# Switch.net
KiCad netlist of a schematic drawn in Altium Designer
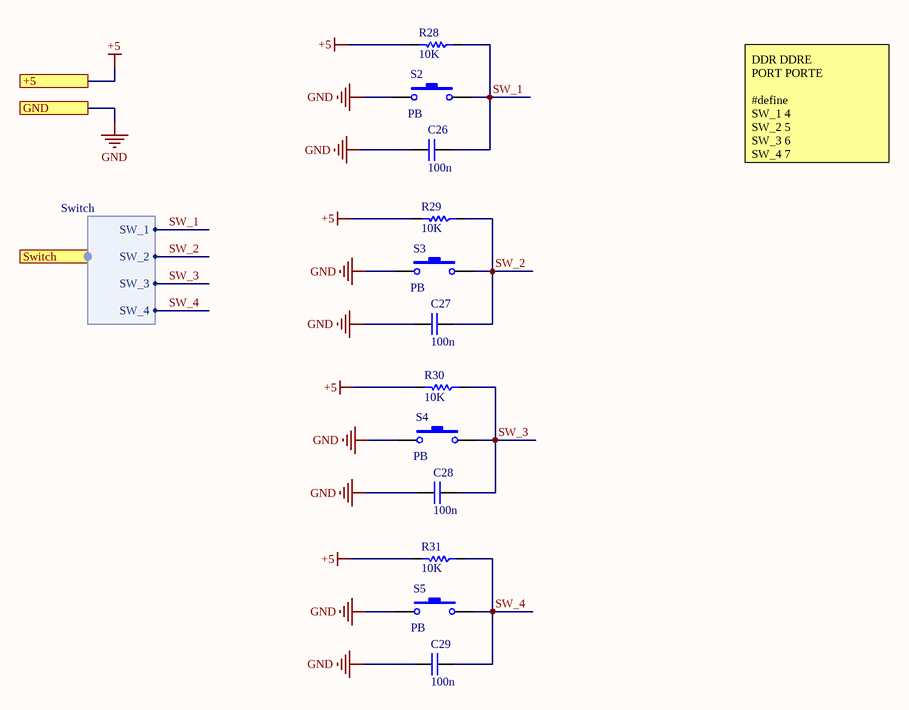
[diagram p0: Switch.SchDoc]

(export (version "E")
  (design (tool "Eeschema 10.0.6"))
  (components
    (comp (ref "C26")
      (value "100n")
      (footprint "CAP 1206/3216")
      (description "Bipolar ceramic capacitor SMD")
      (fields (field (name "VALIDATION") "Valid"))
      (libsource (lib "aKaReZa") (part "Cap_Multi_SMD_100nF_1206"))
    )
    (comp (ref "C27")
      (value "100n")
      (footprint "CAP 1206/3216")
      (description "Bipolar ceramic capacitor SMD")
      (fields (field (name "VALIDATION") "Valid"))
      (libsource (lib "aKaReZa") (part "Cap_Multi_SMD_100nF_1206"))
    )
    (comp (ref "C28")
      (value "100n")
      (footprint "CAP 1206/3216")
      (description "Bipolar ceramic capacitor SMD")
      (fields (field (name "VALIDATION") "Valid"))
      (libsource (lib "aKaReZa") (part "Cap_Multi_SMD_100nF_1206"))
    )
    (comp (ref "C29")
      (value "100n")
      (footprint "CAP 1206/3216")
      (description "Bipolar ceramic capacitor SMD")
      (fields (field (name "VALIDATION") "Valid"))
      (libsource (lib "aKaReZa") (part "Cap_Multi_SMD_100nF_1206"))
    )
    (comp (ref "R28")
      (value "10K")
      (footprint "RES 1206 (3216X08L)")
      (description "Resistor")
      (fields (field (name "VALIDATION") "Valid"))
      (libsource (lib "aKaReZa") (part "Res_SMD_1206"))
    )
    (comp (ref "R29")
      (value "10K")
      (footprint "RES 1206 (3216X08L)")
      (description "Resistor")
      (fields (field (name "VALIDATION") "Valid"))
      (libsource (lib "aKaReZa") (part "Res_SMD_1206"))
    )
    (comp (ref "R30")
      (value "10K")
      (footprint "RES 1206 (3216X08L)")
      (description "Resistor")
      (fields (field (name "VALIDATION") "Valid"))
      (libsource (lib "aKaReZa") (part "Res_SMD_1206"))
    )
    (comp (ref "R31")
      (value "10K")
      (footprint "RES 1206 (3216X08L)")
      (description "Resistor")
      (fields (field (name "VALIDATION") "Valid"))
      (libsource (lib "aKaReZa") (part "Res_SMD_1206"))
    )
    (comp (ref "S2")
      (value "PB")
      (footprint "SW_PB_SMD_2PIN_SPST_6X3X2")
      (description "SMT Tactile ‎Switch")
      (fields (field (name "VALIDATION") "Valid"))
      (libsource (lib "aKaReZa") (part "SW_PushButton_2_SMD"))
    )
    (comp (ref "S3")
      (value "PB")
      (footprint "SW_PB_SMD_2PIN_SPST_6X3X2")
      (description "SMT Tactile ‎Switch")
      (fields (field (name "VALIDATION") "Valid"))
      (libsource (lib "aKaReZa") (part "SW_PushButton_2_SMD"))
    )
    (comp (ref "S4")
      (value "PB")
      (footprint "SW_PB_SMD_2PIN_SPST_6X3X2")
      (description "SMT Tactile ‎Switch")
      (fields (field (name "VALIDATION") "Valid"))
      (libsource (lib "aKaReZa") (part "SW_PushButton_2_SMD"))
    )
    (comp (ref "S5")
      (value "PB")
      (footprint "SW_PB_SMD_2PIN_SPST_6X3X2")
      (description "SMT Tactile ‎Switch")
      (fields (field (name "VALIDATION") "Valid"))
      (libsource (lib "aKaReZa") (part "SW_PushButton_2_SMD"))
    )
  )
  (nets
    (net (code "2") (name "+5") (class "Default")
      (node (ref "R28") (pin "2") (pinfunction "2_2") (pintype "passive"))
      (node (ref "R29") (pin "2") (pinfunction "2_2") (pintype "passive"))
      (node (ref "R30") (pin "2") (pinfunction "2_2") (pintype "passive"))
      (node (ref "R31") (pin "2") (pinfunction "2_2") (pintype "passive"))
    )
    (net (code "3") (name "/SW_1") (class "Default")
      (node (ref "C26") (pin "1") (pinfunction "1_1") (pintype "passive"))
      (node (ref "R28") (pin "1") (pinfunction "1_1") (pintype "passive"))
      (node (ref "S2") (pin "2") (pinfunction "2_2") (pintype "passive"))
    )
    (net (code "4") (name "/SW_2") (class "Default")
      (node (ref "C27") (pin "1") (pinfunction "1_1") (pintype "passive"))
      (node (ref "R29") (pin "1") (pinfunction "1_1") (pintype "passive"))
      (node (ref "S3") (pin "2") (pinfunction "2_2") (pintype "passive"))
    )
    (net (code "5") (name "/SW_3") (class "Default")
      (node (ref "C28") (pin "1") (pinfunction "1_1") (pintype "passive"))
      (node (ref "R30") (pin "1") (pinfunction "1_1") (pintype "passive"))
      (node (ref "S4") (pin "2") (pinfunction "2_2") (pintype "passive"))
    )
    (net (code "6") (name "/SW_4") (class "Default")
      (node (ref "C29") (pin "1") (pinfunction "1_1") (pintype "passive"))
      (node (ref "R31") (pin "1") (pinfunction "1_1") (pintype "passive"))
      (node (ref "S5") (pin "2") (pinfunction "2_2") (pintype "passive"))
    )
    (net (code "8") (name "GND") (class "Default")
      (node (ref "C26") (pin "2") (pinfunction "2_2") (pintype "passive"))
      (node (ref "C27") (pin "2") (pinfunction "2_2") (pintype "passive"))
      (node (ref "C28") (pin "2") (pinfunction "2_2") (pintype "passive"))
      (node (ref "C29") (pin "2") (pinfunction "2_2") (pintype "passive"))
      (node (ref "S2") (pin "1") (pinfunction "1_1") (pintype "passive"))
      (node (ref "S3") (pin "1") (pinfunction "1_1") (pintype "passive"))
      (node (ref "S4") (pin "1") (pinfunction "1_1") (pintype "passive"))
      (node (ref "S5") (pin "1") (pinfunction "1_1") (pintype "passive"))
    )
  )
)
